# SecSysDem_HW.net
KiCad netlist of a schematic drawn in EAGLE
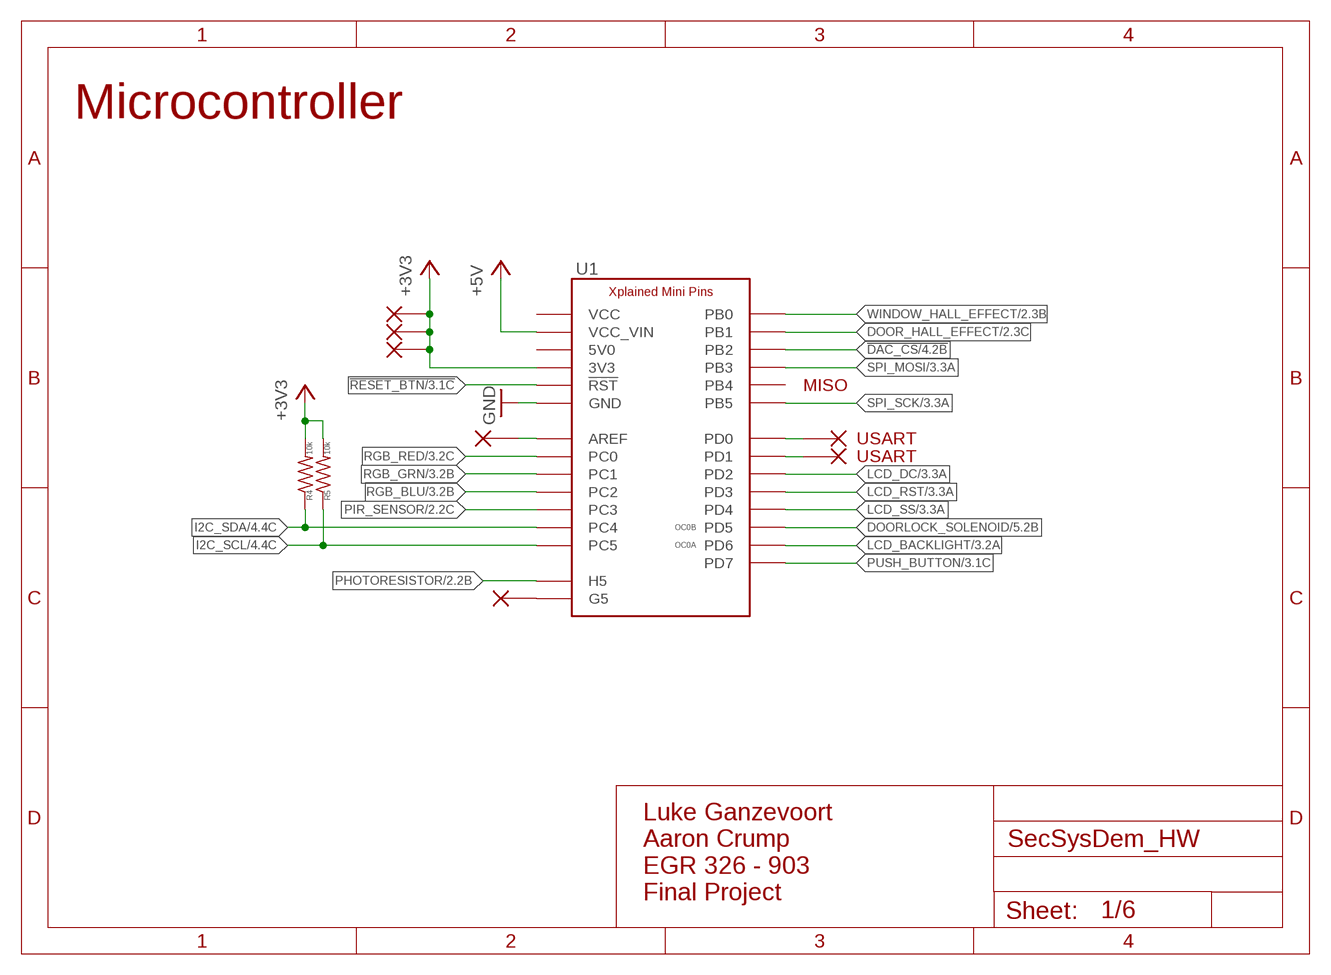
[diagram p0: schematic, sheet 1]
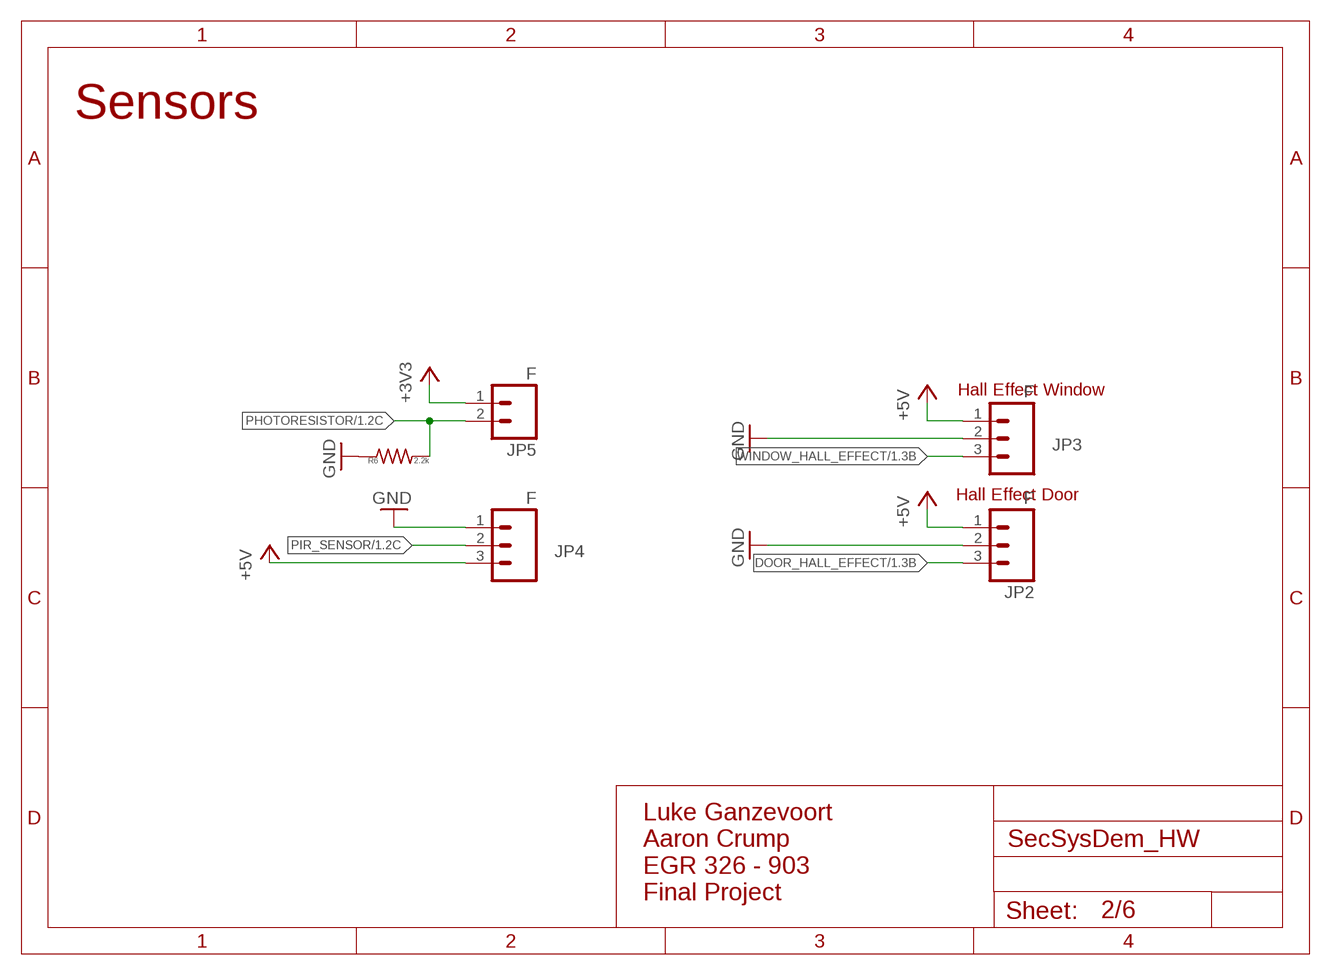
[diagram p1: schematic, sheet 2]
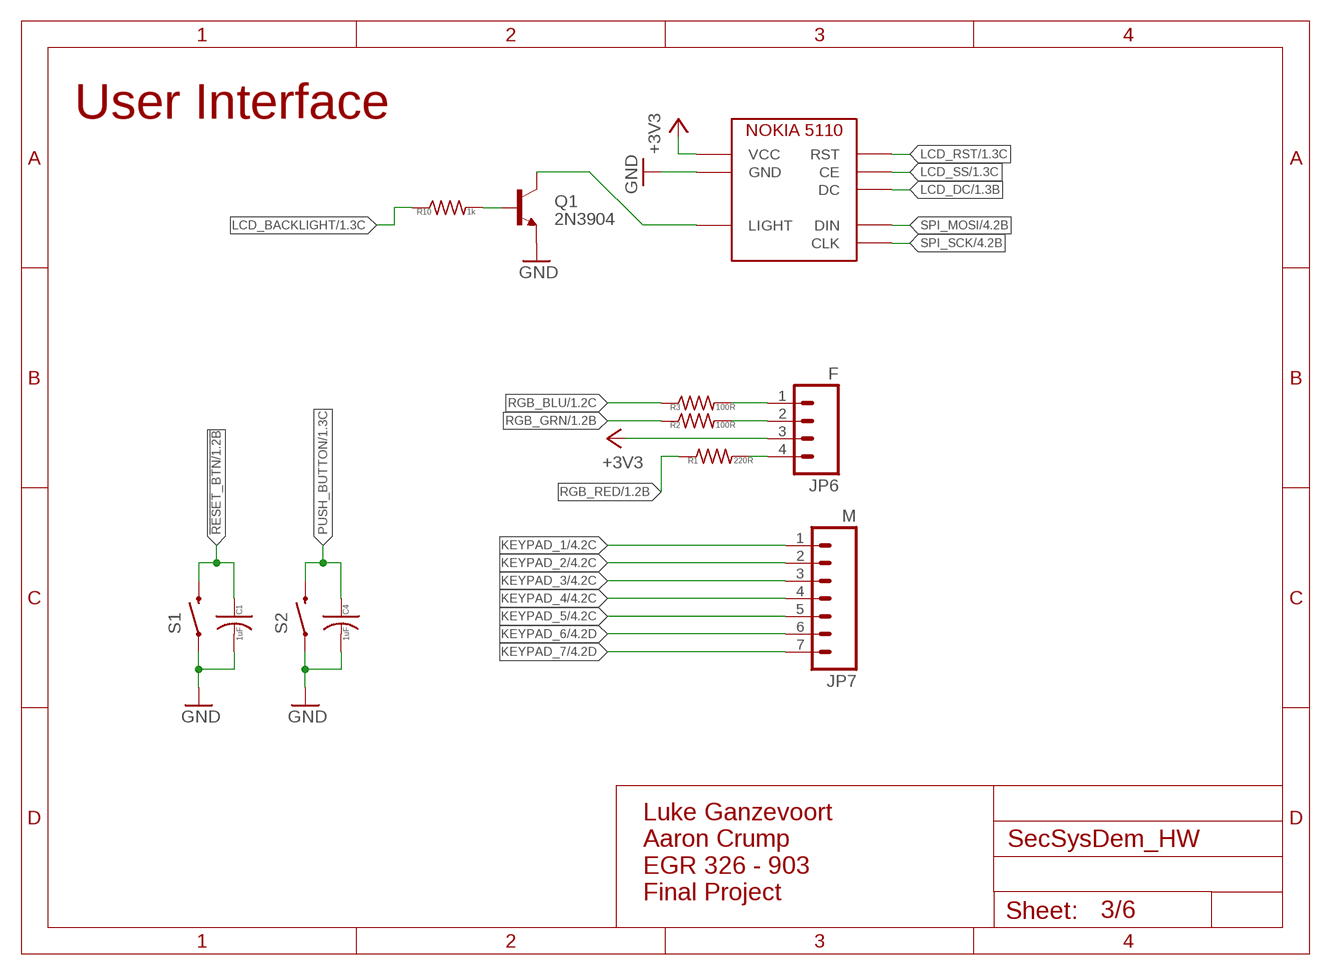
[diagram p2: schematic, sheet 3]
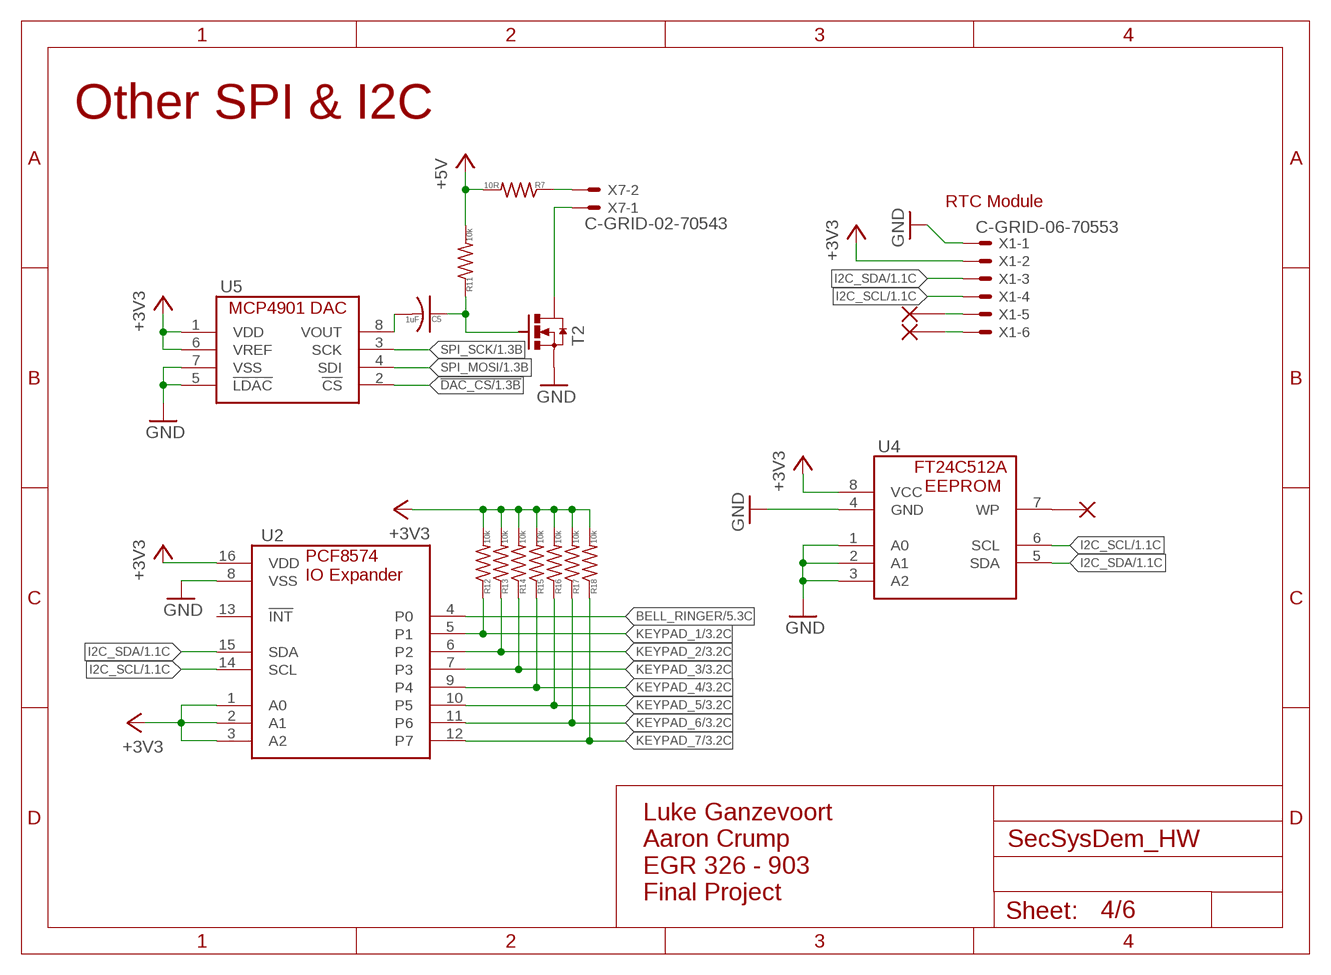
[diagram p3: schematic, sheet 4]
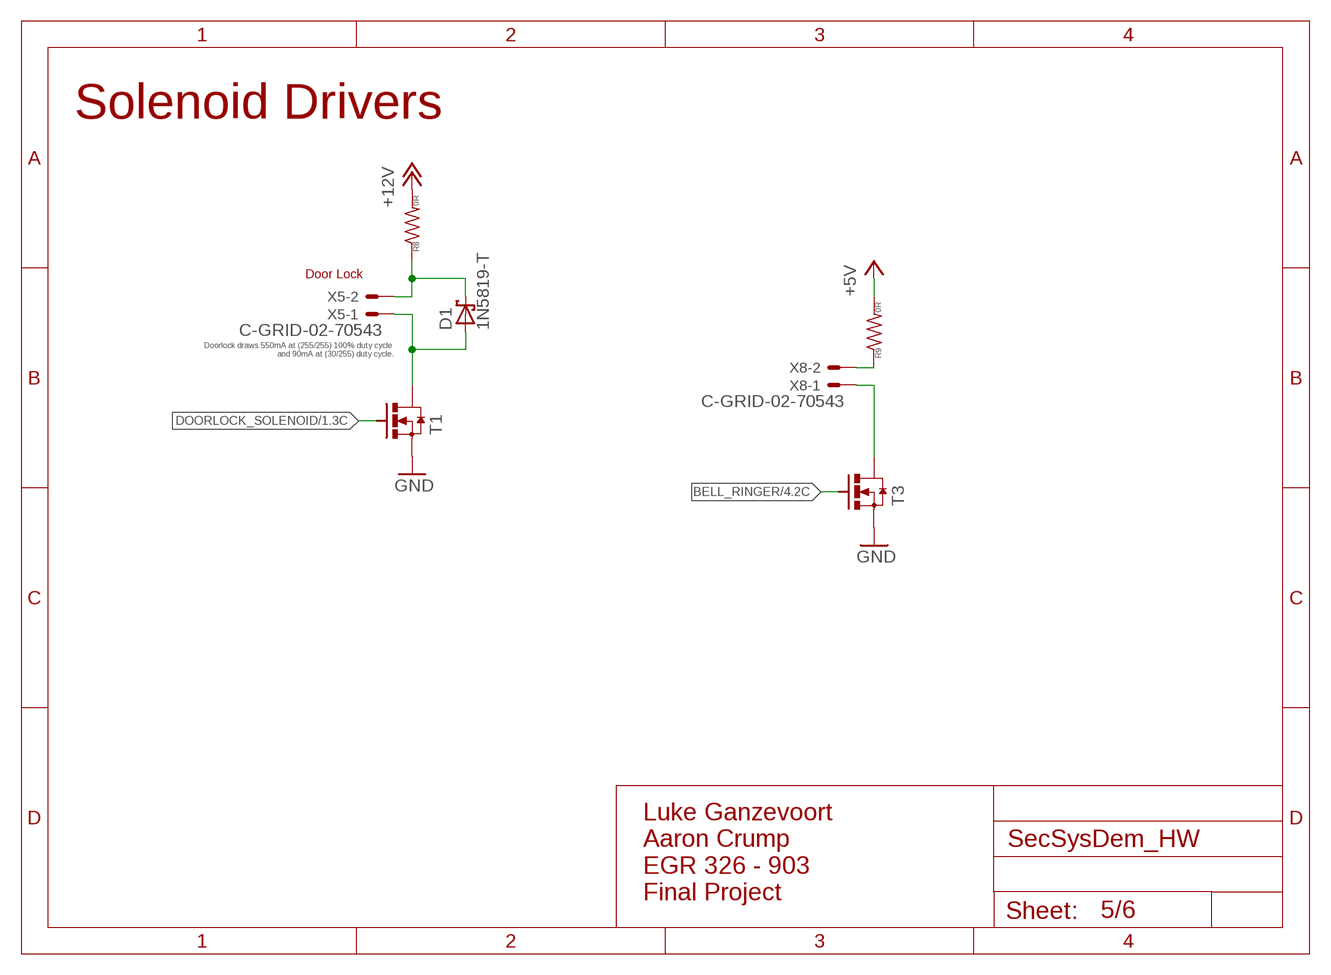
[diagram p4: schematic, sheet 5]
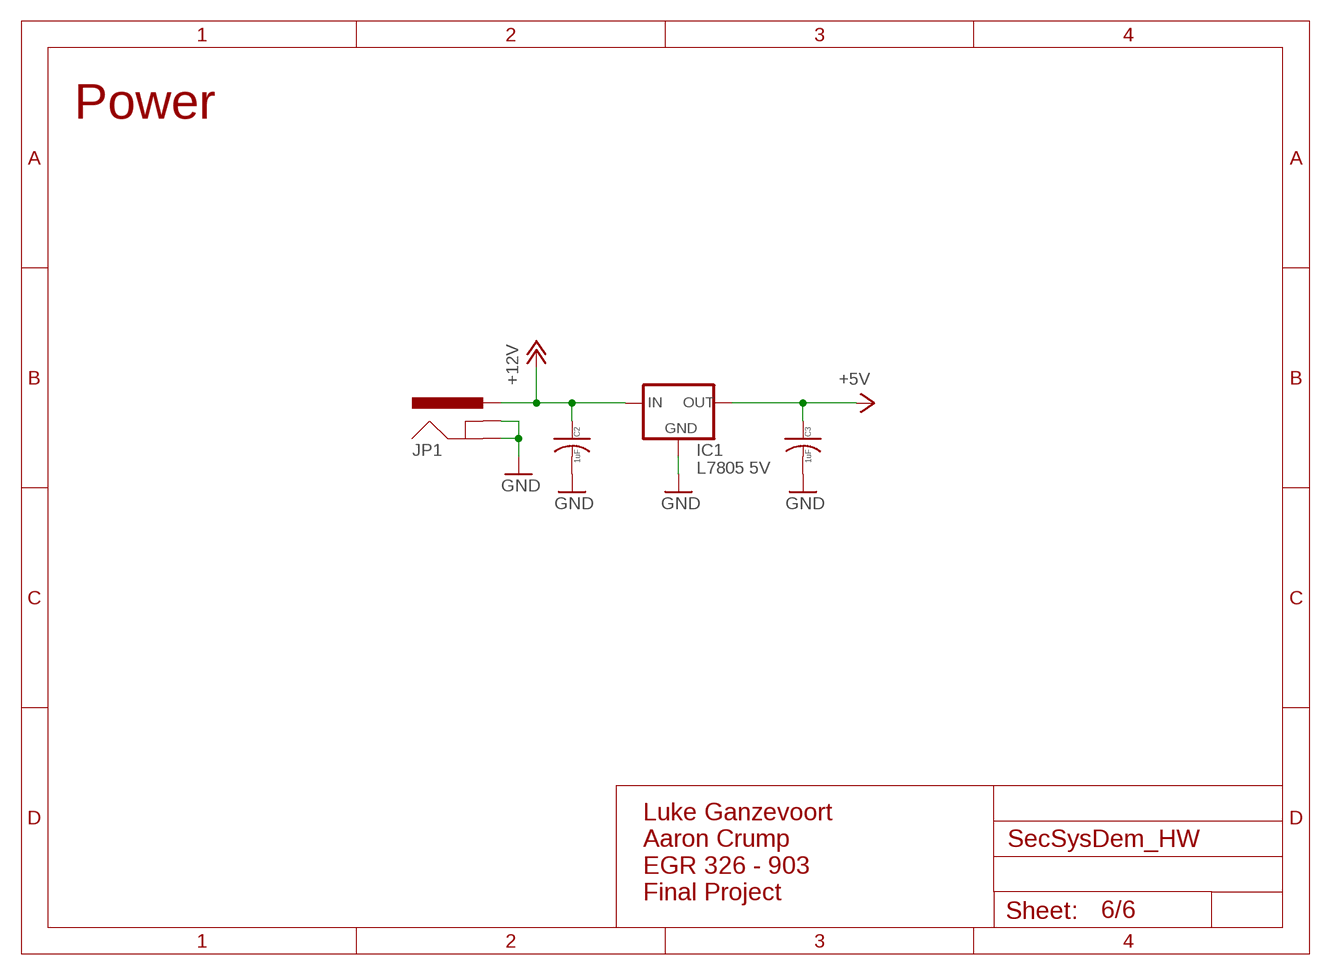
[diagram p5: schematic, sheet 6]

(export (version "E")
  (design (tool "Eeschema 10.0.6"))
  (components
    (comp (ref "R4")
      (value "10k")
      (footprint "eagle-import:C0805")
      (libsource (lib "eagle-import") (part "RESISTOR0805"))
    )
    (comp (ref "R5")
      (value "10k")
      (footprint "eagle-import:C0805")
      (libsource (lib "eagle-import") (part "RESISTOR0805"))
    )
    (comp (ref "U1")
      (value "XPLAINED_MINI_PINOUT")
      (footprint "eagle-import:XPLAINED_MINI_PINS")
      (libsource (lib "eagle-import") (part "XPLAINED_MINI_PINOUT"))
    )
    (comp (ref "V3")
      (value "TXD")
      (footprint "eagle-import:VIA1")
      (libsource (lib "eagle-import") (part "VIA1"))
    )
    (comp (ref "V4")
      (value "RXD")
      (footprint "eagle-import:VIA1")
      (libsource (lib "eagle-import") (part "VIA1"))
    )
    (comp (ref "V5")
      (value "G5")
      (footprint "eagle-import:VIA1")
      (libsource (lib "eagle-import") (part "VIA1"))
    )
    (comp (ref "V6")
      (value "AREF")
      (footprint "eagle-import:VIA1")
      (libsource (lib "eagle-import") (part "VIA1"))
    )
    (comp (ref "V7")
      (value "3v3")
      (footprint "eagle-import:VIA1")
      (libsource (lib "eagle-import") (part "VIA1"))
    )
    (comp (ref "V8")
      (value "3v3")
      (footprint "eagle-import:VIA1")
      (libsource (lib "eagle-import") (part "VIA1"))
    )
    (comp (ref "V9")
      (value "3v3")
      (footprint "eagle-import:VIA1")
      (libsource (lib "eagle-import") (part "VIA1"))
    )
    (comp (ref "D1")
      (value "1N5819-T")
      (footprint "eagle-import:DO41-7.6")
      (libsource (lib "eagle-import") (part "1N5819-T"))
    )
    (comp (ref "R8")
      (value "0R")
      (footprint "eagle-import:C0805")
      (libsource (lib "eagle-import") (part "RESISTOR0805"))
    )
    (comp (ref "R9")
      (value "0R")
      (footprint "eagle-import:C0805")
      (libsource (lib "eagle-import") (part "RESISTOR0805"))
    )
    (comp (ref "T1")
      (value "MOSFET_NCHANNEL_ENHANCEMENT2N7002,215")
      (footprint "eagle-import:SOT23")
      (fields (field (name "POWER") "830 mW"))
      (libsource (lib "eagle-import") (part "MOSFET_NCHANNEL_ENHANCEMENT2N7002,215"))
    )
    (comp (ref "T3")
      (value "MOSFET_NCHANNEL_ENHANCEMENT2N7002,215")
      (footprint "eagle-import:SOT23")
      (fields (field (name "POWER") "830 mW"))
      (libsource (lib "eagle-import") (part "MOSFET_NCHANNEL_ENHANCEMENT2N7002,215"))
    )
    (comp (ref "X5")
      (value "C-GRID-02-70543")
      (footprint "eagle-import:70543-02")
      (libsource (lib "eagle-import") (part "C-GRID-02-70543"))
    )
    (comp (ref "X8")
      (value "C-GRID-02-70543")
      (footprint "eagle-import:70543-02")
      (libsource (lib "eagle-import") (part "C-GRID-02-70543"))
    )
    (comp (ref "C1")
      (value "1uF")
      (footprint "eagle-import:C0805")
      (libsource (lib "eagle-import") (part "CAPACITOR0805"))
    )
    (comp (ref "C4")
      (value "1uF")
      (footprint "eagle-import:C0805")
      (libsource (lib "eagle-import") (part "CAPACITOR0805"))
    )
    (comp (ref "JP6")
      (value "F")
      (footprint "eagle-import:1X04")
      (libsource (lib "eagle-import") (part "M04PTH"))
    )
    (comp (ref "JP7")
      (value "M")
      (footprint "eagle-import:1X07")
      (libsource (lib "eagle-import") (part "M07"))
    )
    (comp (ref "Q1")
      (value "2N3904")
      (footprint "eagle-import:TO-92-AMMO")
      (libsource (lib "eagle-import") (part "TRANSISTOR_NPNBC547"))
    )
    (comp (ref "R1")
      (value "220R")
      (footprint "eagle-import:C0805")
      (libsource (lib "eagle-import") (part "RESISTOR0805"))
    )
    (comp (ref "R2")
      (value "100R")
      (footprint "eagle-import:C0805")
      (libsource (lib "eagle-import") (part "RESISTOR0805"))
    )
    (comp (ref "R3")
      (value "100R")
      (footprint "eagle-import:C0805")
      (libsource (lib "eagle-import") (part "RESISTOR0805"))
    )
    (comp (ref "R10")
      (value "1k")
      (footprint "eagle-import:C0805")
      (libsource (lib "eagle-import") (part "RESISTOR0805"))
    )
    (comp (ref "S1")
      (value "TACTILE_SWITCHTHROUGH_HOLE")
      (footprint "eagle-import:TACTILE_SWITCH")
      (libsource (lib "eagle-import") (part "TACTILE_SWITCHTHROUGH_HOLE"))
    )
    (comp (ref "S2")
      (value "TACTILE_SWITCHTHROUGH_HOLE")
      (footprint "eagle-import:TACTILE_SWITCH")
      (libsource (lib "eagle-import") (part "TACTILE_SWITCHTHROUGH_HOLE"))
    )
    (comp (ref "U$3")
      (value "NOKIA_5110_LCD")
      (footprint "eagle-import:NOKIA_5110")
      (libsource (lib "eagle-import") (part "NOKIA_5110_LCD"))
    )
    (comp (ref "JP2")
      (value "F")
      (footprint "eagle-import:1X03")
      (libsource (lib "eagle-import") (part "M03PTH"))
    )
    (comp (ref "JP3")
      (value "F")
      (footprint "eagle-import:1X03")
      (libsource (lib "eagle-import") (part "M03PTH"))
    )
    (comp (ref "JP4")
      (value "F")
      (footprint "eagle-import:1X03")
      (libsource (lib "eagle-import") (part "M03PTH"))
    )
    (comp (ref "JP5")
      (value "F")
      (footprint "eagle-import:1X02")
      (libsource (lib "eagle-import") (part "M02PTH"))
    )
    (comp (ref "R6")
      (value "2.2k")
      (footprint "eagle-import:C0805")
      (libsource (lib "eagle-import") (part "RESISTOR0805"))
    )
    (comp (ref "C5")
      (value "1uF")
      (footprint "eagle-import:C0805")
      (libsource (lib "eagle-import") (part "CAPACITOR0805"))
    )
    (comp (ref "R7")
      (value "10R")
      (footprint "eagle-import:C0805")
      (libsource (lib "eagle-import") (part "RESISTOR0805"))
    )
    (comp (ref "R11")
      (value "10k")
      (footprint "eagle-import:C0805")
      (libsource (lib "eagle-import") (part "RESISTOR0805"))
    )
    (comp (ref "R12")
      (value "10k")
      (footprint "eagle-import:C0805")
      (libsource (lib "eagle-import") (part "RESISTOR0805"))
    )
    (comp (ref "R13")
      (value "10k")
      (footprint "eagle-import:C0805")
      (libsource (lib "eagle-import") (part "RESISTOR0805"))
    )
    (comp (ref "R14")
      (value "10k")
      (footprint "eagle-import:C0805")
      (libsource (lib "eagle-import") (part "RESISTOR0805"))
    )
    (comp (ref "R15")
      (value "10k")
      (footprint "eagle-import:C0805")
      (libsource (lib "eagle-import") (part "RESISTOR0805"))
    )
    (comp (ref "R16")
      (value "10k")
      (footprint "eagle-import:C0805")
      (libsource (lib "eagle-import") (part "RESISTOR0805"))
    )
    (comp (ref "R17")
      (value "10k")
      (footprint "eagle-import:C0805")
      (libsource (lib "eagle-import") (part "RESISTOR0805"))
    )
    (comp (ref "R18")
      (value "10k")
      (footprint "eagle-import:C0805")
      (libsource (lib "eagle-import") (part "RESISTOR0805"))
    )
    (comp (ref "T2")
      (value "MOSFET_NCHANNEL_ENHANCEMENT2N7002,215")
      (footprint "eagle-import:SOT23")
      (fields (field (name "POWER") "830 mW"))
      (libsource (lib "eagle-import") (part "MOSFET_NCHANNEL_ENHANCEMENT2N7002,215"))
    )
    (comp (ref "U2")
      (value "PCF8574_IO_EXPANDER")
      (footprint "eagle-import:DIL16")
      (libsource (lib "eagle-import") (part "PCF8574_IO_EXPANDER"))
    )
    (comp (ref "U4")
      (value "FT24C512A")
      (footprint "eagle-import:8-SOIC")
      (libsource (lib "eagle-import") (part "FT24C512A"))
    )
    (comp (ref "U5")
      (value "MCP4901-E/SN")
      (footprint "eagle-import:8-SOIC")
      (libsource (lib "eagle-import") (part "MCP4901-E/SN"))
    )
    (comp (ref "V1")
      (value "WP")
      (footprint "eagle-import:VIA1")
      (libsource (lib "eagle-import") (part "VIA1"))
    )
    (comp (ref "V2")
      (value "32k")
      (footprint "eagle-import:VIA1")
      (libsource (lib "eagle-import") (part "VIA1"))
    )
    (comp (ref "V10")
      (value "SQW")
      (footprint "eagle-import:VIA1")
      (libsource (lib "eagle-import") (part "VIA1"))
    )
    (comp (ref "X1")
      (value "C-GRID-06-70553")
      (footprint "eagle-import:70553-06")
      (libsource (lib "eagle-import") (part "C-GRID-06-70553"))
    )
    (comp (ref "X7")
      (value "C-GRID-02-70543")
      (footprint "eagle-import:70543-02")
      (libsource (lib "eagle-import") (part "C-GRID-02-70543"))
    )
    (comp (ref "C2")
      (value "1uF")
      (footprint "eagle-import:C0805")
      (libsource (lib "eagle-import") (part "CAPACITOR0805"))
    )
    (comp (ref "C3")
      (value "1uF")
      (footprint "eagle-import:C0805")
      (libsource (lib "eagle-import") (part "CAPACITOR0805"))
    )
    (comp (ref "IC1")
      (value "L7805 5V")
      (footprint "eagle-import:78XXL")
      (libsource (lib "eagle-import") (part "78XXL"))
    )
    (comp (ref "JP1")
      (value "POWER_JACKPTH_BREAD")
      (footprint "eagle-import:POWER_JACK_PTH_BREAD")
      (libsource (lib "eagle-import") (part "POWER_JACKPTH_BREAD"))
    )
  )
  (nets
    (net (code "1") (name "+3V3") (class "Default")
      (node (ref "JP5") (pin "1") (pinfunction "1_1") (pintype "passive"))
      (node (ref "JP6") (pin "3") (pinfunction "3_3") (pintype "passive"))
      (node (ref "R12") (pin "2") (pinfunction "2_2") (pintype "passive"))
      (node (ref "R13") (pin "2") (pinfunction "2_2") (pintype "passive"))
      (node (ref "R14") (pin "2") (pinfunction "2_2") (pintype "passive"))
      (node (ref "R15") (pin "2") (pinfunction "2_2") (pintype "passive"))
      (node (ref "R16") (pin "2") (pinfunction "2_2") (pintype "passive"))
      (node (ref "R17") (pin "2") (pinfunction "2_2") (pintype "passive"))
      (node (ref "R18") (pin "2") (pinfunction "2_2") (pintype "passive"))
      (node (ref "R4") (pin "2") (pinfunction "2_2") (pintype "passive"))
      (node (ref "R5") (pin "2") (pinfunction "2_2") (pintype "passive"))
      (node (ref "U$3") (pin "P$14") (pinfunction "VCC_P$14") (pintype "bidirectional"))
      (node (ref "U$3") (pin "P$6") (pinfunction "VCC_P$6") (pintype "bidirectional"))
      (node (ref "U1") (pin "P$11") (pinfunction "3V3_P$11") (pintype "bidirectional"))
      (node (ref "U2") (pin "1") (pinfunction "A0_1") (pintype "bidirectional"))
      (node (ref "U2") (pin "16") (pinfunction "VDD_16") (pintype "bidirectional"))
      (node (ref "U2") (pin "2") (pinfunction "A1_2") (pintype "bidirectional"))
      (node (ref "U2") (pin "3") (pinfunction "A2_3") (pintype "bidirectional"))
      (node (ref "U4") (pin "8") (pinfunction "VCC_8") (pintype "bidirectional"))
      (node (ref "U5") (pin "1") (pinfunction "VDD_1") (pintype "bidirectional"))
      (node (ref "U5") (pin "6") (pinfunction "VREF_6") (pintype "bidirectional"))
      (node (ref "V7") (pin "P$1") (pinfunction "P$1_P$1") (pintype "bidirectional"))
      (node (ref "V8") (pin "P$1") (pinfunction "P$1_P$1") (pintype "bidirectional"))
      (node (ref "V9") (pin "P$1") (pinfunction "P$1_P$1") (pintype "bidirectional"))
      (node (ref "X1") (pin "2") (pinfunction "S_2") (pintype "passive"))
    )
    (net (code "2") (name "+5V") (class "Default")
      (node (ref "C3") (pin "1") (pinfunction "POS_1") (pintype "passive"))
      (node (ref "IC1") (pin "OUT") (pinfunction "OUT_OUT") (pintype "passive"))
      (node (ref "JP2") (pin "1") (pinfunction "1_1") (pintype "passive"))
      (node (ref "JP3") (pin "1") (pinfunction "1_1") (pintype "passive"))
      (node (ref "JP4") (pin "3") (pinfunction "3_3") (pintype "passive"))
      (node (ref "R11") (pin "2") (pinfunction "2_2") (pintype "passive"))
      (node (ref "R7") (pin "2") (pinfunction "2_2") (pintype "passive"))
      (node (ref "R9") (pin "2") (pinfunction "2_2") (pintype "passive"))
      (node (ref "U1") (pin "P$7") (pinfunction "VCC_VIN_P$7") (pintype "bidirectional"))
    )
    (net (code "3") (name "+12V") (class "Default")
      (node (ref "C2") (pin "1") (pinfunction "POS_1") (pintype "passive"))
      (node (ref "IC1") (pin "IN") (pinfunction "IN_IN") (pintype "input"))
      (node (ref "JP1") (pin "PWR") (pinfunction "PWR_PWR") (pintype "bidirectional"))
      (node (ref "R8") (pin "2") (pinfunction "2_2") (pintype "passive"))
    )
    (net (code "4") (name "BELL_RINGER") (class "Default")
      (node (ref "T3") (pin "1") (pinfunction "G_1") (pintype "passive"))
      (node (ref "U2") (pin "4") (pinfunction "P0_4") (pintype "bidirectional"))
    )
    (net (code "5") (name "DOORLOCK_SOLENOID") (class "Default")
      (node (ref "T1") (pin "1") (pinfunction "G_1") (pintype "passive"))
      (node (ref "U1") (pin "P$20") (pinfunction "PD5_P$20") (pintype "bidirectional"))
    )
    (net (code "6") (name "DOOR_HALL_EFFECT") (class "Default")
      (node (ref "JP2") (pin "3") (pinfunction "3_3") (pintype "passive"))
      (node (ref "U1") (pin "P$24") (pinfunction "PB1_P$24") (pintype "bidirectional"))
    )
    (net (code "7") (name "GND") (class "Default")
      (node (ref "C1") (pin "2") (pinfunction "NEG_2") (pintype "passive"))
      (node (ref "C2") (pin "2") (pinfunction "NEG_2") (pintype "passive"))
      (node (ref "C3") (pin "2") (pinfunction "NEG_2") (pintype "passive"))
      (node (ref "C4") (pin "2") (pinfunction "NEG_2") (pintype "passive"))
      (node (ref "IC1") (pin "GND") (pinfunction "GND_GND") (pintype "input"))
      (node (ref "JP1") (pin "GND") (pinfunction "GND_GND") (pintype "bidirectional"))
      (node (ref "JP1") (pin "GNDBREAK") (pinfunction "GNDBREAK_GNDBREAK") (pintype "bidirectional"))
      (node (ref "JP2") (pin "2") (pinfunction "2_2") (pintype "passive"))
      (node (ref "JP3") (pin "2") (pinfunction "2_2") (pintype "passive"))
      (node (ref "JP4") (pin "1") (pinfunction "1_1") (pintype "passive"))
      (node (ref "Q1") (pin "3") (pinfunction "E_3") (pintype "passive"))
      (node (ref "R6") (pin "1") (pinfunction "1_1") (pintype "passive"))
      (node (ref "S1") (pin "1") (pinfunction "1_1") (pintype "passive"))
      (node (ref "S1") (pin "2") (pinfunction "1_2") (pintype "passive"))
      (node (ref "S2") (pin "1") (pinfunction "1_1") (pintype "passive"))
      (node (ref "S2") (pin "2") (pinfunction "1_2") (pintype "passive"))
      (node (ref "T1") (pin "2") (pinfunction "S_2") (pintype "passive"))
      (node (ref "T2") (pin "2") (pinfunction "S_2") (pintype "passive"))
      (node (ref "T3") (pin "2") (pinfunction "S_2") (pintype "passive"))
      (node (ref "U$3") (pin "P$16") (pinfunction "GND_P$16") (pintype "bidirectional"))
      (node (ref "U$3") (pin "P$8") (pinfunction "GND_P$8") (pintype "bidirectional"))
      (node (ref "U1") (pin "P$29") (pinfunction "GND_P$29") (pintype "bidirectional"))
      (node (ref "U1") (pin "P$8") (pinfunction "GND_P$8") (pintype "bidirectional"))
      (node (ref "U1") (pin "P$9") (pinfunction "GND_P$9") (pintype "bidirectional"))
      (node (ref "U2") (pin "8") (pinfunction "VSS_8") (pintype "bidirectional"))
      (node (ref "U4") (pin "1") (pinfunction "A0_1") (pintype "bidirectional"))
      (node (ref "U4") (pin "2") (pinfunction "A1_2") (pintype "bidirectional"))
      (node (ref "U4") (pin "3") (pinfunction "A2_3") (pintype "bidirectional"))
      (node (ref "U4") (pin "4") (pinfunction "GND_4") (pintype "bidirectional"))
      (node (ref "U5") (pin "5") (pinfunction "~{LDAC}_5") (pintype "bidirectional"))
      (node (ref "U5") (pin "7") (pinfunction "VSS_7") (pintype "bidirectional"))
      (node (ref "X1") (pin "1") (pinfunction "S_1") (pintype "passive"))
    )
    (net (code "8") (name "I2C_SCL") (class "Default")
      (node (ref "R5") (pin "1") (pinfunction "1_1") (pintype "passive"))
      (node (ref "U1") (pin "P$1") (pinfunction "PC5_P$1") (pintype "bidirectional"))
      (node (ref "U1") (pin "P$32") (pinfunction "PC5_P$32") (pintype "bidirectional"))
      (node (ref "U2") (pin "14") (pinfunction "SCL_14") (pintype "bidirectional"))
      (node (ref "U4") (pin "6") (pinfunction "SCL_6") (pintype "bidirectional"))
      (node (ref "X1") (pin "4") (pinfunction "S_4") (pintype "passive"))
    )
    (net (code "9") (name "I2C_SDA") (class "Default")
      (node (ref "R4") (pin "1") (pinfunction "1_1") (pintype "passive"))
      (node (ref "U1") (pin "P$2") (pinfunction "PC4_P$2") (pintype "bidirectional"))
      (node (ref "U1") (pin "P$31") (pinfunction "PC4_P$31") (pintype "bidirectional"))
      (node (ref "U2") (pin "15") (pinfunction "SDA_15") (pintype "bidirectional"))
      (node (ref "U4") (pin "5") (pinfunction "SDA_5") (pintype "bidirectional"))
      (node (ref "X1") (pin "3") (pinfunction "S_3") (pintype "passive"))
    )
    (net (code "10") (name "KEYPAD_1") (class "Default")
      (node (ref "JP7") (pin "1") (pinfunction "1_1") (pintype "passive"))
      (node (ref "R12") (pin "1") (pinfunction "1_1") (pintype "passive"))
      (node (ref "U2") (pin "5") (pinfunction "P1_5") (pintype "bidirectional"))
    )
    (net (code "11") (name "KEYPAD_2") (class "Default")
      (node (ref "JP7") (pin "2") (pinfunction "2_2") (pintype "passive"))
      (node (ref "R13") (pin "1") (pinfunction "1_1") (pintype "passive"))
      (node (ref "U2") (pin "6") (pinfunction "P2_6") (pintype "bidirectional"))
    )
    (net (code "12") (name "KEYPAD_3") (class "Default")
      (node (ref "JP7") (pin "3") (pinfunction "3_3") (pintype "passive"))
      (node (ref "R14") (pin "1") (pinfunction "1_1") (pintype "passive"))
      (node (ref "U2") (pin "7") (pinfunction "P3_7") (pintype "bidirectional"))
    )
    (net (code "13") (name "KEYPAD_4") (class "Default")
      (node (ref "JP7") (pin "4") (pinfunction "4_4") (pintype "passive"))
      (node (ref "R15") (pin "1") (pinfunction "1_1") (pintype "passive"))
      (node (ref "U2") (pin "9") (pinfunction "P4_9") (pintype "bidirectional"))
    )
    (net (code "14") (name "KEYPAD_5") (class "Default")
      (node (ref "JP7") (pin "5") (pinfunction "5_5") (pintype "passive"))
      (node (ref "R16") (pin "1") (pinfunction "1_1") (pintype "passive"))
      (node (ref "U2") (pin "10") (pinfunction "P5_10") (pintype "bidirectional"))
    )
    (net (code "15") (name "KEYPAD_6") (class "Default")
      (node (ref "JP7") (pin "6") (pinfunction "6_6") (pintype "passive"))
      (node (ref "R17") (pin "1") (pinfunction "1_1") (pintype "passive"))
      (node (ref "U2") (pin "11") (pinfunction "P6_11") (pintype "bidirectional"))
    )
    (net (code "16") (name "KEYPAD_7") (class "Default")
      (node (ref "JP7") (pin "7") (pinfunction "7_7") (pintype "passive"))
      (node (ref "R18") (pin "1") (pinfunction "1_1") (pintype "passive"))
      (node (ref "U2") (pin "12") (pinfunction "P7_12") (pintype "bidirectional"))
    )
    (net (code "17") (name "LCD_BACKLIGHT") (class "Default")
      (node (ref "R10") (pin "1") (pinfunction "1_1") (pintype "passive"))
      (node (ref "U1") (pin "P$21") (pinfunction "PD6_P$21") (pintype "bidirectional"))
    )
    (net (code "18") (name "LCD_DC") (class "Default")
      (node (ref "U$3") (pin "P$11") (pinfunction "DC_P$11") (pintype "bidirectional"))
      (node (ref "U$3") (pin "P$3") (pinfunction "DC_P$3") (pintype "bidirectional"))
      (node (ref "U1") (pin "P$17") (pinfunction "PD2_P$17") (pintype "bidirectional"))
    )
    (net (code "19") (name "LCD_RST") (class "Default")
      (node (ref "U$3") (pin "P$1") (pinfunction "RST_P$1") (pintype "bidirectional"))
      (node (ref "U$3") (pin "P$9") (pinfunction "RST_P$9") (pintype "bidirectional"))
      (node (ref "U1") (pin "P$18") (pinfunction "PD3_P$18") (pintype "bidirectional"))
    )
    (net (code "20") (name "LCD_SS") (class "Default")
      (node (ref "U$3") (pin "P$10") (pinfunction "CE_P$10") (pintype "bidirectional"))
      (node (ref "U$3") (pin "P$2") (pinfunction "CE_P$2") (pintype "bidirectional"))
      (node (ref "U1") (pin "P$19") (pinfunction "PD4_P$19") (pintype "bidirectional"))
    )
    (net (code "21") (name "Net-(C5-NEG)") (class "Default")
      (node (ref "C5") (pin "2") (pinfunction "NEG_2") (pintype "passive"))
      (node (ref "U5") (pin "8") (pinfunction "VOUT_8") (pintype "bidirectional"))
    )
    (net (code "22") (name "Net-(C5-POS)") (class "Default")
      (node (ref "C5") (pin "1") (pinfunction "POS_1") (pintype "passive"))
      (node (ref "R11") (pin "1") (pinfunction "1_1") (pintype "passive"))
      (node (ref "T2") (pin "1") (pinfunction "G_1") (pintype "passive"))
    )
    (net (code "23") (name "Net-(JP6-Pad1)") (class "Default")
      (node (ref "JP6") (pin "1") (pinfunction "1_1") (pintype "passive"))
      (node (ref "R3") (pin "2") (pinfunction "2_2") (pintype "passive"))
    )
    (net (code "24") (name "Net-(JP6-Pad2)") (class "Default")
      (node (ref "JP6") (pin "2") (pinfunction "2_2") (pintype "passive"))
      (node (ref "R2") (pin "2") (pinfunction "2_2") (pintype "passive"))
    )
    (net (code "25") (name "Net-(JP6-Pad4)") (class "Default")
      (node (ref "JP6") (pin "4") (pinfunction "4_4") (pintype "passive"))
      (node (ref "R1") (pin "2") (pinfunction "2_2") (pintype "passive"))
    )
    (net (code "26") (name "Net-(Q1-B)") (class "Default")
      (node (ref "Q1") (pin "2") (pinfunction "B_2") (pintype "passive"))
      (node (ref "R10") (pin "2") (pinfunction "2_2") (pintype "passive"))
    )
    (net (code "27") (name "Net-(Q1-C)") (class "Default")
      (node (ref "Q1") (pin "1") (pinfunction "C_1") (pintype "passive"))
      (node (ref "U$3") (pin "P$15") (pinfunction "LIGHT_P$15") (pintype "bidirectional"))
      (node (ref "U$3") (pin "P$7") (pinfunction "LIGHT_P$7") (pintype "bidirectional"))
    )
    (net (code "28") (name "Net-(T1-D)") (class "Default")
      (node (ref "D1") (pin "A") (pinfunction "A_A") (pintype "passive"))
      (node (ref "T1") (pin "3") (pinfunction "D_3") (pintype "passive"))
      (node (ref "X5") (pin "1") (pinfunction "S_1") (pintype "passive"))
    )
    (net (code "29") (name "Net-(T2-D)") (class "Default")
      (node (ref "T2") (pin "3") (pinfunction "D_3") (pintype "passive"))
      (node (ref "X7") (pin "1") (pinfunction "S_1") (pintype "passive"))
    )
    (net (code "30") (name "Net-(T3-D)") (class "Default")
      (node (ref "T3") (pin "3") (pinfunction "D_3") (pintype "passive"))
      (node (ref "X8") (pin "1") (pinfunction "S_1") (pintype "passive"))
    )
    (net (code "31") (name "Net-(U1-AREF)") (class "Default")
      (node (ref "U1") (pin "P$30") (pinfunction "AREF_P$30") (pintype "bidirectional"))
      (node (ref "V6") (pin "P$1") (pinfunction "P$1_P$1") (pintype "bidirectional"))
    )
    (net (code "32") (name "Net-(U1-G5)") (class "Default")
      (node (ref "U1") (pin "P$34") (pinfunction "G5_P$34") (pintype "bidirectional"))
      (node (ref "V5") (pin "P$1") (pinfunction "P$1_P$1") (pintype "bidirectional"))
    )
    (net (code "33") (name "Net-(U1-PD0)") (class "Default")
      (node (ref "U1") (pin "P$15") (pinfunction "PD0_P$15") (pintype "bidirectional"))
      (node (ref "V3") (pin "P$1") (pinfunction "P$1_P$1") (pintype "bidirectional"))
    )
    (net (code "34") (name "Net-(U1-PD1)") (class "Default")
      (node (ref "U1") (pin "P$16") (pinfunction "PD1_P$16") (pintype "bidirectional"))
      (node (ref "V4") (pin "P$1") (pinfunction "P$1_P$1") (pintype "bidirectional"))
    )
    (net (code "35") (name "Net-(U4-WP)") (class "Default")
      (node (ref "U4") (pin "7") (pinfunction "WP_7") (pintype "bidirectional"))
      (node (ref "V1") (pin "P$1") (pinfunction "P$1_P$1") (pintype "bidirectional"))
    )
    (net (code "36") (name "Net-(X1E-S)") (class "Default")
      (node (ref "V10") (pin "P$1") (pinfunction "P$1_P$1") (pintype "bidirectional"))
      (node (ref "X1") (pin "5") (pinfunction "S_5") (pintype "passive"))
    )
    (net (code "37") (name "Net-(X1F-S)") (class "Default")
      (node (ref "V2") (pin "P$1") (pinfunction "P$1_P$1") (pintype "bidirectional"))
      (node (ref "X1") (pin "6") (pinfunction "S_6") (pintype "passive"))
    )
    (net (code "38") (name "Net-(X5B-S)") (class "Default")
      (node (ref "D1") (pin "C") (pinfunction "C_C") (pintype "passive"))
      (node (ref "R8") (pin "1") (pinfunction "1_1") (pintype "passive"))
      (node (ref "X5") (pin "2") (pinfunction "S_2") (pintype "passive"))
    )
    (net (code "39") (name "Net-(X7B-S)") (class "Default")
      (node (ref "R7") (pin "1") (pinfunction "1_1") (pintype "passive"))
      (node (ref "X7") (pin "2") (pinfunction "S_2") (pintype "passive"))
    )
    (net (code "40") (name "Net-(X8B-S)") (class "Default")
      (node (ref "R9") (pin "1") (pinfunction "1_1") (pintype "passive"))
      (node (ref "X8") (pin "2") (pinfunction "S_2") (pintype "passive"))
    )
    (net (code "41") (name "PHOTORESISTOR") (class "Default")
      (node (ref "JP5") (pin "2") (pinfunction "2_2") (pintype "passive"))
      (node (ref "R6") (pin "2") (pinfunction "2_2") (pintype "passive"))
      (node (ref "U1") (pin "P$33") (pinfunction "H5_P$33") (pintype "bidirectional"))
    )
    (net (code "42") (name "PIR_SENSOR") (class "Default")
      (node (ref "JP4") (pin "2") (pinfunction "2_2") (pintype "passive"))
      (node (ref "U1") (pin "P$3") (pinfunction "PC3_P$3") (pintype "bidirectional"))
    )
    (net (code "43") (name "PUSH_BUTTON") (class "Default")
      (node (ref "C4") (pin "1") (pinfunction "POS_1") (pintype "passive"))
      (node (ref "S2") (pin "3") (pinfunction "2_3") (pintype "passive"))
      (node (ref "S2") (pin "4") (pinfunction "2_4") (pintype "passive"))
      (node (ref "U1") (pin "P$22") (pinfunction "PD7_P$22") (pintype "bidirectional"))
    )
    (net (code "44") (name "RGB_BLU") (class "Default")
      (node (ref "R3") (pin "1") (pinfunction "1_1") (pintype "passive"))
      (node (ref "U1") (pin "P$4") (pinfunction "PC2_P$4") (pintype "bidirectional"))
    )
    (net (code "45") (name "RGB_GRN") (class "Default")
      (node (ref "R2") (pin "1") (pinfunction "1_1") (pintype "passive"))
      (node (ref "U1") (pin "P$5") (pinfunction "PC1_P$5") (pintype "bidirectional"))
    )
    (net (code "46") (name "RGB_RED") (class "Default")
      (node (ref "R1") (pin "1") (pinfunction "1_1") (pintype "passive"))
      (node (ref "U1") (pin "P$6") (pinfunction "PC0_P$6") (pintype "bidirectional"))
    )
    (net (code "47") (name "SPI_MOSI") (class "Default")
      (node (ref "U$3") (pin "P$12") (pinfunction "DIN_P$12") (pintype "bidirectional"))
      (node (ref "U$3") (pin "P$4") (pinfunction "DIN_P$4") (pintype "bidirectional"))
      (node (ref "U1") (pin "P$26") (pinfunction "PB3_P$26") (pintype "bidirectional"))
      (node (ref "U5") (pin "4") (pinfunction "SDI_4") (pintype "bidirectional"))
    )
    (net (code "48") (name "SPI_SCK") (class "Default")
      (node (ref "U$3") (pin "P$13") (pinfunction "CLK_P$13") (pintype "bidirectional"))
      (node (ref "U$3") (pin "P$5") (pinfunction "CLK_P$5") (pintype "bidirectional"))
      (node (ref "U1") (pin "P$28") (pinfunction "PB5_P$28") (pintype "bidirectional"))
      (node (ref "U5") (pin "3") (pinfunction "SCK_3") (pintype "bidirectional"))
    )
    (net (code "49") (name "WINDOW_HALL_EFFECT") (class "Default")
      (node (ref "JP3") (pin "3") (pinfunction "3_3") (pintype "passive"))
      (node (ref "U1") (pin "P$23") (pinfunction "PB0_P$23") (pintype "bidirectional"))
    )
    (net (code "50") (name "unconnected-(U1-5V0-PadP$10)") (class "Default")
      (node (ref "U1") (pin "P$10") (pinfunction "5V0_P$10") (pintype "bidirectional"))
    )
    (net (code "51") (name "unconnected-(U1-PB4-PadP$27)") (class "Default")
      (node (ref "U1") (pin "P$27") (pinfunction "PB4_P$27") (pintype "bidirectional"))
    )
    (net (code "52") (name "unconnected-(U1-VCC-PadP$13)") (class "Default")
      (node (ref "U1") (pin "P$13") (pinfunction "VCC_P$13") (pintype "bidirectional"))
    )
    (net (code "53") (name "unconnected-(U2-~{INT}-Pad13)") (class "Default")
      (node (ref "U2") (pin "13") (pinfunction "~{INT}_13") (pintype "bidirectional"))
    )
    (net (code "54") (name "~{DAC_CS}") (class "Default")
      (node (ref "U1") (pin "P$25") (pinfunction "PB2_P$25") (pintype "bidirectional"))
      (node (ref "U5") (pin "2") (pinfunction "~{CS}_2") (pintype "bidirectional"))
    )
    (net (code "55") (name "~{RESET_BTN}") (class "Default")
      (node (ref "C1") (pin "1") (pinfunction "POS_1") (pintype "passive"))
      (node (ref "S1") (pin "3") (pinfunction "2_3") (pintype "passive"))
      (node (ref "S1") (pin "4") (pinfunction "2_4") (pintype "passive"))
      (node (ref "U1") (pin "P$12") (pinfunction "~{RST}_P$12") (pintype "bidirectional"))
    )
  )
)
